# Ethernet_PMOD.net
KiCad netlist of a schematic drawn in Altium Designer
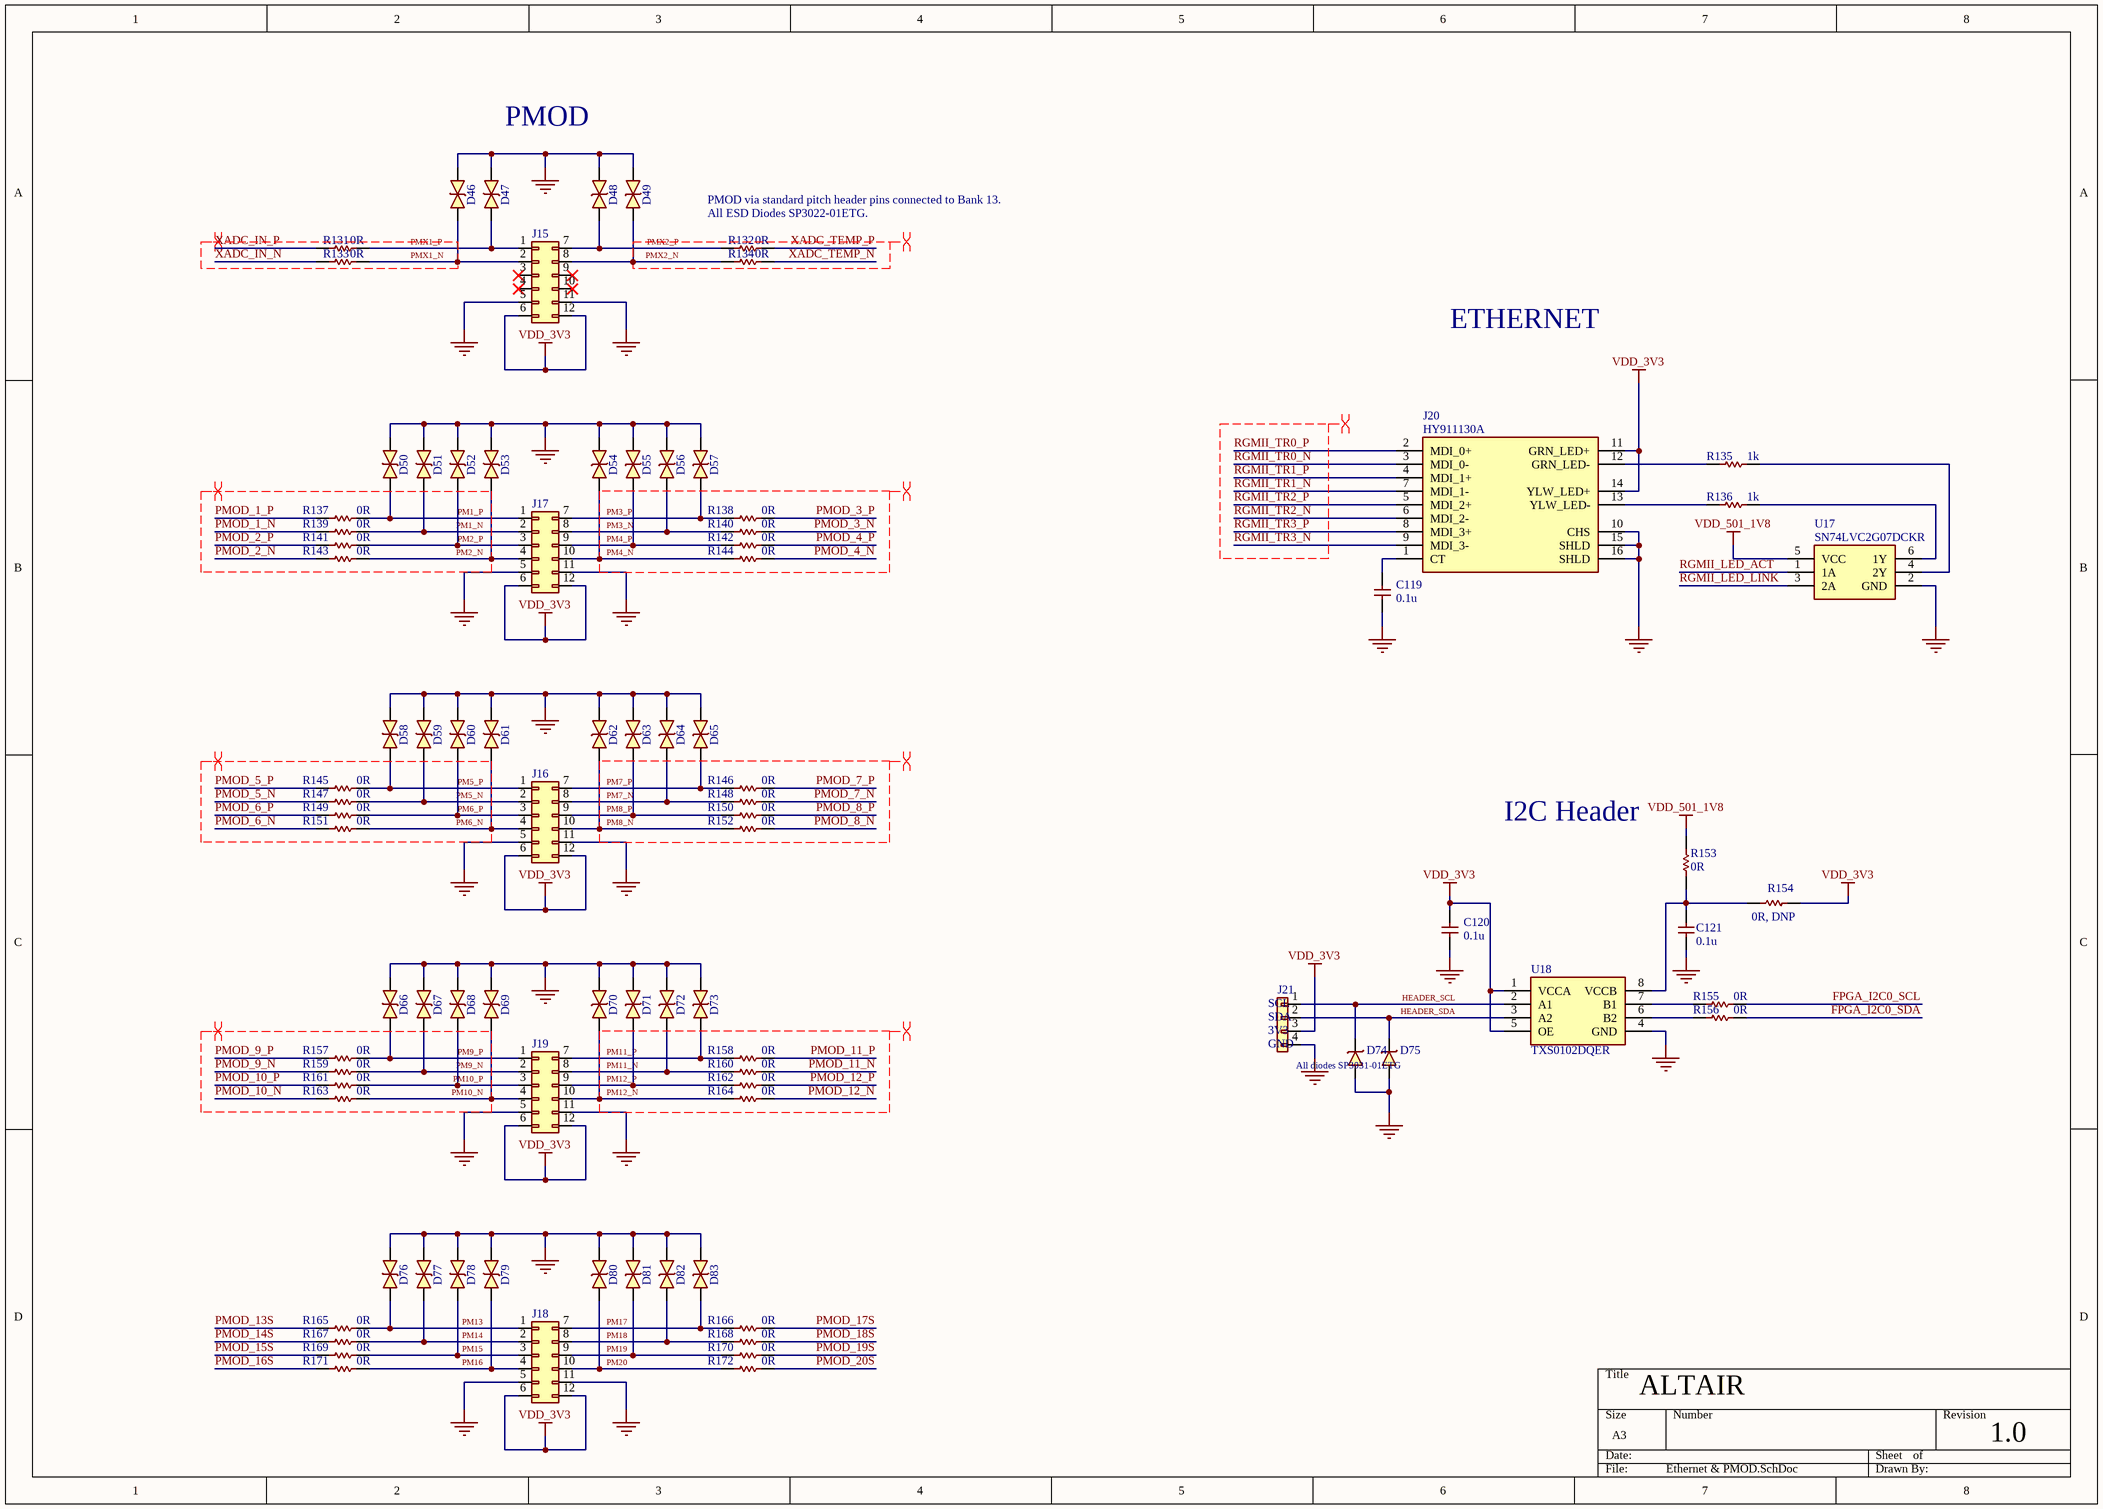
[diagram p0: Ethernet & PMOD.SchDoc]

(export (version "E")
  (design (tool "Eeschema 10.0.6"))
  (components
    (comp (ref "C119")
      (value "0.1u")
      (footprint "CAP_0402")
      (description "Capacitor SMD 0402")
      (fields (field (name "PART NO") "CL05B104KO5NNNC") (field (name "JLCPCB PART #") "C338112"))
      (libsource (lib "personalGenericLib") (part "CAP_0402"))
    )
    (comp (ref "C120")
      (value "0.1u")
      (footprint "CAP_0402")
      (description "Capacitor SMD 0402")
      (fields (field (name "PART NO") "CL05B104KO5NNNC") (field (name "JLCPCB PART #") "C338112"))
      (libsource (lib "personalGenericLib") (part "CAP_0402"))
    )
    (comp (ref "C121")
      (value "0.1u")
      (footprint "CAP_0402")
      (description "Capacitor SMD 0402")
      (fields (field (name "PART NO") "CL05B104KO5NNNC") (field (name "JLCPCB PART #") "C338112"))
      (libsource (lib "personalGenericLib") (part "CAP_0402"))
    )
    (comp (ref "D46")
      (value "SP3022-01ETG")
      (footprint "SP302201ETGNM")
      (description "TVS Diode (Bi-directional)")
      (fields (field (name "JLCPCB PART #") "C126840"))
      (libsource (lib "personalGenericLib") (part "SP3022-01ETG"))
    )
    (comp (ref "D47")
      (value "SP3022-01ETG")
      (footprint "SP302201ETGNM")
      (description "TVS Diode (Bi-directional)")
      (fields (field (name "JLCPCB PART #") "C126840"))
      (libsource (lib "personalGenericLib") (part "SP3022-01ETG"))
    )
    (comp (ref "D48")
      (value "SP3022-01ETG")
      (footprint "SP302201ETGNM")
      (description "TVS Diode (Bi-directional)")
      (fields (field (name "JLCPCB PART #") "C126840"))
      (libsource (lib "personalGenericLib") (part "SP3022-01ETG"))
    )
    (comp (ref "D49")
      (value "SP3022-01ETG")
      (footprint "SP302201ETGNM")
      (description "TVS Diode (Bi-directional)")
      (fields (field (name "JLCPCB PART #") "C126840"))
      (libsource (lib "personalGenericLib") (part "SP3022-01ETG"))
    )
    (comp (ref "D50")
      (value "SP3022-01ETG")
      (footprint "SP302201ETGNM")
      (description "TVS Diode (Bi-directional)")
      (fields (field (name "JLCPCB PART #") "C126840"))
      (libsource (lib "personalGenericLib") (part "SP3022-01ETG"))
    )
    (comp (ref "D51")
      (value "SP3022-01ETG")
      (footprint "SP302201ETGNM")
      (description "TVS Diode (Bi-directional)")
      (fields (field (name "JLCPCB PART #") "C126840"))
      (libsource (lib "personalGenericLib") (part "SP3022-01ETG"))
    )
    (comp (ref "D52")
      (value "SP3022-01ETG")
      (footprint "SP302201ETGNM")
      (description "TVS Diode (Bi-directional)")
      (fields (field (name "JLCPCB PART #") "C126840"))
      (libsource (lib "personalGenericLib") (part "SP3022-01ETG"))
    )
    (comp (ref "D53")
      (value "SP3022-01ETG")
      (footprint "SP302201ETGNM")
      (description "TVS Diode (Bi-directional)")
      (fields (field (name "JLCPCB PART #") "C126840"))
      (libsource (lib "personalGenericLib") (part "SP3022-01ETG"))
    )
    (comp (ref "D54")
      (value "SP3022-01ETG")
      (footprint "SP302201ETGNM")
      (description "TVS Diode (Bi-directional)")
      (fields (field (name "JLCPCB PART #") "C126840"))
      (libsource (lib "personalGenericLib") (part "SP3022-01ETG"))
    )
    (comp (ref "D55")
      (value "SP3022-01ETG")
      (footprint "SP302201ETGNM")
      (description "TVS Diode (Bi-directional)")
      (fields (field (name "JLCPCB PART #") "C126840"))
      (libsource (lib "personalGenericLib") (part "SP3022-01ETG"))
    )
    (comp (ref "D56")
      (value "SP3022-01ETG")
      (footprint "SP302201ETGNM")
      (description "TVS Diode (Bi-directional)")
      (fields (field (name "JLCPCB PART #") "C126840"))
      (libsource (lib "personalGenericLib") (part "SP3022-01ETG"))
    )
    (comp (ref "D57")
      (value "SP3022-01ETG")
      (footprint "SP302201ETGNM")
      (description "TVS Diode (Bi-directional)")
      (fields (field (name "JLCPCB PART #") "C126840"))
      (libsource (lib "personalGenericLib") (part "SP3022-01ETG"))
    )
    (comp (ref "D58")
      (value "SP3022-01ETG")
      (footprint "SP302201ETGNM")
      (description "TVS Diode (Bi-directional)")
      (fields (field (name "JLCPCB PART #") "C126840"))
      (libsource (lib "personalGenericLib") (part "SP3022-01ETG"))
    )
    (comp (ref "D59")
      (value "SP3022-01ETG")
      (footprint "SP302201ETGNM")
      (description "TVS Diode (Bi-directional)")
      (fields (field (name "JLCPCB PART #") "C126840"))
      (libsource (lib "personalGenericLib") (part "SP3022-01ETG"))
    )
    (comp (ref "D60")
      (value "SP3022-01ETG")
      (footprint "SP302201ETGNM")
      (description "TVS Diode (Bi-directional)")
      (fields (field (name "JLCPCB PART #") "C126840"))
      (libsource (lib "personalGenericLib") (part "SP3022-01ETG"))
    )
    (comp (ref "D61")
      (value "SP3022-01ETG")
      (footprint "SP302201ETGNM")
      (description "TVS Diode (Bi-directional)")
      (fields (field (name "JLCPCB PART #") "C126840"))
      (libsource (lib "personalGenericLib") (part "SP3022-01ETG"))
    )
    (comp (ref "D62")
      (value "SP3022-01ETG")
      (footprint "SP302201ETGNM")
      (description "TVS Diode (Bi-directional)")
      (fields (field (name "JLCPCB PART #") "C126840"))
      (libsource (lib "personalGenericLib") (part "SP3022-01ETG"))
    )
    (comp (ref "D63")
      (value "SP3022-01ETG")
      (footprint "SP302201ETGNM")
      (description "TVS Diode (Bi-directional)")
      (fields (field (name "JLCPCB PART #") "C126840"))
      (libsource (lib "personalGenericLib") (part "SP3022-01ETG"))
    )
    (comp (ref "D64")
      (value "SP3022-01ETG")
      (footprint "SP302201ETGNM")
      (description "TVS Diode (Bi-directional)")
      (fields (field (name "JLCPCB PART #") "C126840"))
      (libsource (lib "personalGenericLib") (part "SP3022-01ETG"))
    )
    (comp (ref "D65")
      (value "SP3022-01ETG")
      (footprint "SP302201ETGNM")
      (description "TVS Diode (Bi-directional)")
      (fields (field (name "JLCPCB PART #") "C126840"))
      (libsource (lib "personalGenericLib") (part "SP3022-01ETG"))
    )
    (comp (ref "D66")
      (value "SP3022-01ETG")
      (footprint "SP302201ETGNM")
      (description "TVS Diode (Bi-directional)")
      (fields (field (name "JLCPCB PART #") "C126840"))
      (libsource (lib "personalGenericLib") (part "SP3022-01ETG"))
    )
    (comp (ref "D67")
      (value "SP3022-01ETG")
      (footprint "SP302201ETGNM")
      (description "TVS Diode (Bi-directional)")
      (fields (field (name "JLCPCB PART #") "C126840"))
      (libsource (lib "personalGenericLib") (part "SP3022-01ETG"))
    )
    (comp (ref "D68")
      (value "SP3022-01ETG")
      (footprint "SP302201ETGNM")
      (description "TVS Diode (Bi-directional)")
      (fields (field (name "JLCPCB PART #") "C126840"))
      (libsource (lib "personalGenericLib") (part "SP3022-01ETG"))
    )
    (comp (ref "D69")
      (value "SP3022-01ETG")
      (footprint "SP302201ETGNM")
      (description "TVS Diode (Bi-directional)")
      (fields (field (name "JLCPCB PART #") "C126840"))
      (libsource (lib "personalGenericLib") (part "SP3022-01ETG"))
    )
    (comp (ref "D70")
      (value "SP3022-01ETG")
      (footprint "SP302201ETGNM")
      (description "TVS Diode (Bi-directional)")
      (fields (field (name "JLCPCB PART #") "C126840"))
      (libsource (lib "personalGenericLib") (part "SP3022-01ETG"))
    )
    (comp (ref "D71")
      (value "SP3022-01ETG")
      (footprint "SP302201ETGNM")
      (description "TVS Diode (Bi-directional)")
      (fields (field (name "JLCPCB PART #") "C126840"))
      (libsource (lib "personalGenericLib") (part "SP3022-01ETG"))
    )
    (comp (ref "D72")
      (value "SP3022-01ETG")
      (footprint "SP302201ETGNM")
      (description "TVS Diode (Bi-directional)")
      (fields (field (name "JLCPCB PART #") "C126840"))
      (libsource (lib "personalGenericLib") (part "SP3022-01ETG"))
    )
    (comp (ref "D73")
      (value "SP3022-01ETG")
      (footprint "SP302201ETGNM")
      (description "TVS Diode (Bi-directional)")
      (fields (field (name "JLCPCB PART #") "C126840"))
      (libsource (lib "personalGenericLib") (part "SP3022-01ETG"))
    )
    (comp (ref "D74")
      (value "SP3031-01ETG")
      (footprint "SP303101ETG")
      (description "TVS Diode (Uni-directional)")
      (fields (field (name "JLCPCB PART #") "C207283"))
      (libsource (lib "personalGenericLib") (part "SP3031-01ETG"))
    )
    (comp (ref "D75")
      (value "SP3031-01ETG")
      (footprint "SP303101ETG")
      (description "TVS Diode (Uni-directional)")
      (fields (field (name "JLCPCB PART #") "C207283"))
      (libsource (lib "personalGenericLib") (part "SP3031-01ETG"))
    )
    (comp (ref "D76")
      (value "SP3022-01ETG")
      (footprint "SP302201ETGNM")
      (description "TVS Diode (Bi-directional)")
      (fields (field (name "JLCPCB PART #") "C126840"))
      (libsource (lib "personalGenericLib") (part "SP3022-01ETG"))
    )
    (comp (ref "D77")
      (value "SP3022-01ETG")
      (footprint "SP302201ETGNM")
      (description "TVS Diode (Bi-directional)")
      (fields (field (name "JLCPCB PART #") "C126840"))
      (libsource (lib "personalGenericLib") (part "SP3022-01ETG"))
    )
    (comp (ref "D78")
      (value "SP3022-01ETG")
      (footprint "SP302201ETGNM")
      (description "TVS Diode (Bi-directional)")
      (fields (field (name "JLCPCB PART #") "C126840"))
      (libsource (lib "personalGenericLib") (part "SP3022-01ETG"))
    )
    (comp (ref "D79")
      (value "SP3022-01ETG")
      (footprint "SP302201ETGNM")
      (description "TVS Diode (Bi-directional)")
      (fields (field (name "JLCPCB PART #") "C126840"))
      (libsource (lib "personalGenericLib") (part "SP3022-01ETG"))
    )
    (comp (ref "D80")
      (value "SP3022-01ETG")
      (footprint "SP302201ETGNM")
      (description "TVS Diode (Bi-directional)")
      (fields (field (name "JLCPCB PART #") "C126840"))
      (libsource (lib "personalGenericLib") (part "SP3022-01ETG"))
    )
    (comp (ref "D81")
      (value "SP3022-01ETG")
      (footprint "SP302201ETGNM")
      (description "TVS Diode (Bi-directional)")
      (fields (field (name "JLCPCB PART #") "C126840"))
      (libsource (lib "personalGenericLib") (part "SP3022-01ETG"))
    )
    (comp (ref "D82")
      (value "SP3022-01ETG")
      (footprint "SP302201ETGNM")
      (description "TVS Diode (Bi-directional)")
      (fields (field (name "JLCPCB PART #") "C126840"))
      (libsource (lib "personalGenericLib") (part "SP3022-01ETG"))
    )
    (comp (ref "D83")
      (value "SP3022-01ETG")
      (footprint "SP302201ETGNM")
      (description "TVS Diode (Bi-directional)")
      (fields (field (name "JLCPCB PART #") "C126840"))
      (libsource (lib "personalGenericLib") (part "SP3022-01ETG"))
    )
    (comp (ref "J15")
      (value "PMOD_HEADER")
      (footprint "PMOD_HEADER")
      (description "NON-Standard 2x6 pin 2.54mm pitch connector. Right Angle")
      (fields (field (name "JLCPCB PART #") "C22373932") (field (name "PART NO") "HC-PM254-8.5H-2x6PW"))
      (libsource (lib "personalGenericLib") (part "PMOD_HEADER"))
    )
    (comp (ref "J16")
      (value "PMOD_HEADER")
      (footprint "PMOD_HEADER")
      (description "NON-Standard 2x6 pin 2.54mm pitch connector. Right Angle")
      (fields (field (name "JLCPCB PART #") "C22373932") (field (name "PART NO") "HC-PM254-8.5H-2x6PW"))
      (libsource (lib "personalGenericLib") (part "PMOD_HEADER"))
    )
    (comp (ref "J17")
      (value "PMOD_HEADER")
      (footprint "PMOD_HEADER")
      (description "NON-Standard 2x6 pin 2.54mm pitch connector. Right Angle")
      (fields (field (name "JLCPCB PART #") "C22373932") (field (name "PART NO") "HC-PM254-8.5H-2x6PW"))
      (libsource (lib "personalGenericLib") (part "PMOD_HEADER"))
    )
    (comp (ref "J18")
      (value "PMOD_HEADER")
      (footprint "PMOD_HEADER")
      (description "NON-Standard 2x6 pin 2.54mm pitch connector. Right Angle")
      (libsource (lib "personalGenericLib") (part "PMOD_HEADER"))
    )
    (comp (ref "J19")
      (value "PMOD_HEADER")
      (footprint "PMOD_HEADER")
      (description "NON-Standard 2x6 pin 2.54mm pitch connector. Right Angle")
      (fields (field (name "JLCPCB PART #") "C22373932") (field (name "PART NO") "HC-PM254-8.5H-2x6PW"))
      (libsource (lib "personalGenericLib") (part "PMOD_HEADER"))
    )
    (comp (ref "J20")
      (value "HY911130A")
      (footprint "HY911130A")
      (description "Ethernet Connector")
      (fields (field (name "JLCPCB PART #") "C55679"))
      (libsource (lib "personalGenericLib") (part "HY911130A"))
    )
    (comp (ref "J21")
      (value "4xHeader")
      (footprint "HDRV4W95P0X254_1X4_1016X254X854P")
      (description "Standard 4 pin 2.54mm pitch connector")
      (fields (field (name "JLCPCB PART #") "C706876") (field (name "PART NO") "X6511WV-04H-C60D30"))
      (libsource (lib "personalGenericLib") (part "4xHeader"))
    )
    (comp (ref "R131")
      (value "0R")
      (footprint "RES_0402")
      (description "Resistor SMD 0402")
      (fields (field (name "JLCPCB PART #") "C60485") (field (name "PART NO") "RC0402JR-070RL"))
      (libsource (lib "personalGenericLib") (part "RES_0402"))
    )
    (comp (ref "R132")
      (value "0R")
      (footprint "RES_0402")
      (description "Resistor SMD 0402")
      (fields (field (name "JLCPCB PART #") "C60485") (field (name "PART NO") "RC0402JR-070RL"))
      (libsource (lib "personalGenericLib") (part "RES_0402"))
    )
    (comp (ref "R133")
      (value "0R")
      (footprint "RES_0402")
      (description "Resistor SMD 0402")
      (fields (field (name "JLCPCB PART #") "C60485") (field (name "PART NO") "RC0402JR-070RL"))
      (libsource (lib "personalGenericLib") (part "RES_0402"))
    )
    (comp (ref "R134")
      (value "0R")
      (footprint "RES_0402")
      (description "Resistor SMD 0402")
      (fields (field (name "JLCPCB PART #") "C60485") (field (name "PART NO") "RC0402JR-070RL"))
      (libsource (lib "personalGenericLib") (part "RES_0402"))
    )
    (comp (ref "R135")
      (value "1k")
      (footprint "RES_0402")
      (description "Resistor SMD 0402")
      (fields (field (name "JLCPCB PART #") "C105637") (field (name "PART NO") "RC0402JR-071KL"))
      (libsource (lib "personalGenericLib") (part "RES_0402"))
    )
    (comp (ref "R136")
      (value "1k")
      (footprint "RES_0402")
      (description "Resistor SMD 0402")
      (fields (field (name "JLCPCB PART #") "C105637") (field (name "PART NO") "RC0402JR-071KL"))
      (libsource (lib "personalGenericLib") (part "RES_0402"))
    )
    (comp (ref "R137")
      (value "0R")
      (footprint "RES_0402")
      (description "Resistor SMD 0402")
      (fields (field (name "JLCPCB PART #") "C60485") (field (name "PART NO") "RC0402JR-070RL"))
      (libsource (lib "personalGenericLib") (part "RES_0402"))
    )
    (comp (ref "R138")
      (value "0R")
      (footprint "RES_0402")
      (description "Resistor SMD 0402")
      (fields (field (name "JLCPCB PART #") "C60485") (field (name "PART NO") "RC0402JR-070RL"))
      (libsource (lib "personalGenericLib") (part "RES_0402"))
    )
    (comp (ref "R139")
      (value "0R")
      (footprint "RES_0402")
      (description "Resistor SMD 0402")
      (fields (field (name "JLCPCB PART #") "C60485") (field (name "PART NO") "RC0402JR-070RL"))
      (libsource (lib "personalGenericLib") (part "RES_0402"))
    )
    (comp (ref "R140")
      (value "0R")
      (footprint "RES_0402")
      (description "Resistor SMD 0402")
      (fields (field (name "JLCPCB PART #") "C60485") (field (name "PART NO") "RC0402JR-070RL"))
      (libsource (lib "personalGenericLib") (part "RES_0402"))
    )
    (comp (ref "R141")
      (value "0R")
      (footprint "RES_0402")
      (description "Resistor SMD 0402")
      (fields (field (name "JLCPCB PART #") "C60485") (field (name "PART NO") "RC0402JR-070RL"))
      (libsource (lib "personalGenericLib") (part "RES_0402"))
    )
    (comp (ref "R142")
      (value "0R")
      (footprint "RES_0402")
      (description "Resistor SMD 0402")
      (fields (field (name "JLCPCB PART #") "C60485") (field (name "PART NO") "RC0402JR-070RL"))
      (libsource (lib "personalGenericLib") (part "RES_0402"))
    )
    (comp (ref "R143")
      (value "0R")
      (footprint "RES_0402")
      (description "Resistor SMD 0402")
      (fields (field (name "JLCPCB PART #") "C60485") (field (name "PART NO") "RC0402JR-070RL"))
      (libsource (lib "personalGenericLib") (part "RES_0402"))
    )
    (comp (ref "R144")
      (value "0R")
      (footprint "RES_0402")
      (description "Resistor SMD 0402")
      (fields (field (name "JLCPCB PART #") "C60485") (field (name "PART NO") "RC0402JR-070RL"))
      (libsource (lib "personalGenericLib") (part "RES_0402"))
    )
    (comp (ref "R145")
      (value "0R")
      (footprint "RES_0402")
      (description "Resistor SMD 0402")
      (fields (field (name "JLCPCB PART #") "C60485") (field (name "PART NO") "RC0402JR-070RL"))
      (libsource (lib "personalGenericLib") (part "RES_0402"))
    )
    (comp (ref "R146")
      (value "0R")
      (footprint "RES_0402")
      (description "Resistor SMD 0402")
      (fields (field (name "JLCPCB PART #") "C60485") (field (name "PART NO") "RC0402JR-070RL"))
      (libsource (lib "personalGenericLib") (part "RES_0402"))
    )
    (comp (ref "R147")
      (value "0R")
      (footprint "RES_0402")
      (description "Resistor SMD 0402")
      (fields (field (name "JLCPCB PART #") "C60485") (field (name "PART NO") "RC0402JR-070RL"))
      (libsource (lib "personalGenericLib") (part "RES_0402"))
    )
    (comp (ref "R148")
      (value "0R")
      (footprint "RES_0402")
      (description "Resistor SMD 0402")
      (fields (field (name "JLCPCB PART #") "C60485") (field (name "PART NO") "RC0402JR-070RL"))
      (libsource (lib "personalGenericLib") (part "RES_0402"))
    )
    (comp (ref "R149")
      (value "0R")
      (footprint "RES_0402")
      (description "Resistor SMD 0402")
      (fields (field (name "JLCPCB PART #") "C60485") (field (name "PART NO") "RC0402JR-070RL"))
      (libsource (lib "personalGenericLib") (part "RES_0402"))
    )
    (comp (ref "R150")
      (value "0R")
      (footprint "RES_0402")
      (description "Resistor SMD 0402")
      (fields (field (name "JLCPCB PART #") "C60485") (field (name "PART NO") "RC0402JR-070RL"))
      (libsource (lib "personalGenericLib") (part "RES_0402"))
    )
    (comp (ref "R151")
      (value "0R")
      (footprint "RES_0402")
      (description "Resistor SMD 0402")
      (fields (field (name "JLCPCB PART #") "C60485") (field (name "PART NO") "RC0402JR-070RL"))
      (libsource (lib "personalGenericLib") (part "RES_0402"))
    )
    (comp (ref "R152")
      (value "0R")
      (footprint "RES_0402")
      (description "Resistor SMD 0402")
      (fields (field (name "JLCPCB PART #") "C60485") (field (name "PART NO") "RC0402JR-070RL"))
      (libsource (lib "personalGenericLib") (part "RES_0402"))
    )
    (comp (ref "R153")
      (value "0R")
      (footprint "RES_0402")
      (description "Resistor SMD 0402")
      (fields (field (name "JLCPCB PART #") "C60485") (field (name "PART NO") "RC0402JR-070RL"))
      (libsource (lib "personalGenericLib") (part "RES_0402"))
    )
    (comp (ref "R154")
      (value "0R, DNP")
      (footprint "RES_0402")
      (description "Resistor SMD 0402")
      (fields (field (name "JLCPCB PART #") "C60485") (field (name "PART NO") "RC0402JR-070RL"))
      (libsource (lib "personalGenericLib") (part "RES_0402"))
    )
    (comp (ref "R155")
      (value "0R")
      (footprint "RES_0402")
      (description "Resistor SMD 0402")
      (fields (field (name "JLCPCB PART #") "C60485") (field (name "PART NO") "RC0402JR-070RL"))
      (libsource (lib "personalGenericLib") (part "RES_0402"))
    )
    (comp (ref "R156")
      (value "0R")
      (footprint "RES_0402")
      (description "Resistor SMD 0402")
      (fields (field (name "JLCPCB PART #") "C60485") (field (name "PART NO") "RC0402JR-070RL"))
      (libsource (lib "personalGenericLib") (part "RES_0402"))
    )
    (comp (ref "R157")
      (value "0R")
      (footprint "RES_0402")
      (description "Resistor SMD 0402")
      (fields (field (name "JLCPCB PART #") "C60485") (field (name "PART NO") "RC0402JR-070RL"))
      (libsource (lib "personalGenericLib") (part "RES_0402"))
    )
    (comp (ref "R158")
      (value "0R")
      (footprint "RES_0402")
      (description "Resistor SMD 0402")
      (fields (field (name "JLCPCB PART #") "C60485") (field (name "PART NO") "RC0402JR-070RL"))
      (libsource (lib "personalGenericLib") (part "RES_0402"))
    )
    (comp (ref "R159")
      (value "0R")
      (footprint "RES_0402")
      (description "Resistor SMD 0402")
      (fields (field (name "JLCPCB PART #") "C60485") (field (name "PART NO") "RC0402JR-070RL"))
      (libsource (lib "personalGenericLib") (part "RES_0402"))
    )
    (comp (ref "R160")
      (value "0R")
      (footprint "RES_0402")
      (description "Resistor SMD 0402")
      (fields (field (name "JLCPCB PART #") "C60485") (field (name "PART NO") "RC0402JR-070RL"))
      (libsource (lib "personalGenericLib") (part "RES_0402"))
    )
    (comp (ref "R161")
      (value "0R")
      (footprint "RES_0402")
      (description "Resistor SMD 0402")
      (fields (field (name "JLCPCB PART #") "C60485") (field (name "PART NO") "RC0402JR-070RL"))
      (libsource (lib "personalGenericLib") (part "RES_0402"))
    )
    (comp (ref "R162")
      (value "0R")
      (footprint "RES_0402")
      (description "Resistor SMD 0402")
      (fields (field (name "JLCPCB PART #") "C60485") (field (name "PART NO") "RC0402JR-070RL"))
      (libsource (lib "personalGenericLib") (part "RES_0402"))
    )
    (comp (ref "R163")
      (value "0R")
      (footprint "RES_0402")
      (description "Resistor SMD 0402")
      (fields (field (name "JLCPCB PART #") "C60485") (field (name "PART NO") "RC0402JR-070RL"))
      (libsource (lib "personalGenericLib") (part "RES_0402"))
    )
    (comp (ref "R164")
      (value "0R")
      (footprint "RES_0402")
      (description "Resistor SMD 0402")
      (fields (field (name "JLCPCB PART #") "C60485") (field (name "PART NO") "RC0402JR-070RL"))
      (libsource (lib "personalGenericLib") (part "RES_0402"))
    )
    (comp (ref "R165")
      (value "0R")
      (footprint "RES_0402")
      (description "Resistor SMD 0402")
      (fields (field (name "JLCPCB PART #") "C60485") (field (name "PART NO") "RC0402JR-070RL"))
      (libsource (lib "personalGenericLib") (part "RES_0402"))
    )
    (comp (ref "R166")
      (value "0R")
      (footprint "RES_0402")
      (description "Resistor SMD 0402")
      (fields (field (name "JLCPCB PART #") "C60485") (field (name "PART NO") "RC0402JR-070RL"))
      (libsource (lib "personalGenericLib") (part "RES_0402"))
    )
    (comp (ref "R167")
      (value "0R")
      (footprint "RES_0402")
      (description "Resistor SMD 0402")
      (fields (field (name "JLCPCB PART #") "C60485") (field (name "PART NO") "RC0402JR-070RL"))
      (libsource (lib "personalGenericLib") (part "RES_0402"))
    )
    (comp (ref "R168")
      (value "0R")
      (footprint "RES_0402")
      (description "Resistor SMD 0402")
      (fields (field (name "JLCPCB PART #") "C60485") (field (name "PART NO") "RC0402JR-070RL"))
      (libsource (lib "personalGenericLib") (part "RES_0402"))
    )
    (comp (ref "R169")
      (value "0R")
      (footprint "RES_0402")
      (description "Resistor SMD 0402")
      (fields (field (name "JLCPCB PART #") "C60485") (field (name "PART NO") "RC0402JR-070RL"))
      (libsource (lib "personalGenericLib") (part "RES_0402"))
    )
    (comp (ref "R170")
      (value "0R")
      (footprint "RES_0402")
      (description "Resistor SMD 0402")
      (fields (field (name "JLCPCB PART #") "C60485") (field (name "PART NO") "RC0402JR-070RL"))
      (libsource (lib "personalGenericLib") (part "RES_0402"))
    )
    (comp (ref "R171")
      (value "0R")
      (footprint "RES_0402")
      (description "Resistor SMD 0402")
      (fields (field (name "JLCPCB PART #") "C60485") (field (name "PART NO") "RC0402JR-070RL"))
      (libsource (lib "personalGenericLib") (part "RES_0402"))
    )
    (comp (ref "R172")
      (value "0R")
      (footprint "RES_0402")
      (description "Resistor SMD 0402")
      (fields (field (name "JLCPCB PART #") "C60485") (field (name "PART NO") "RC0402JR-070RL"))
      (libsource (lib "personalGenericLib") (part "RES_0402"))
    )
    (comp (ref "U17")
      (value "SN74LVC2G07DCKR")
      (footprint "SOT65P210X110-6N")
      (description "Buffer Gate 1 input 1 output")
      (fields (field (name "JLCPCB PART #") "C7849"))
      (libsource (lib "personalGenericLib") (part "SN74LVC2G07DCKR"))
    )
    (comp (ref "U18")
      (value "TXS0102DQER")
      (footprint "SON35P100X140X40-8N")
      (description "I2C UART Voltage Level Translator")
      (fields (field (name "JLCPCB PART #") "C2652935"))
      (libsource (lib "personalGenericLib") (part "TXS0102DQER"))
    )
  )
  (nets
    (net (code "1") (name "/FPGA_I2C0_SCL") (class "Default")
      (node (ref "R155") (pin "2") (pinfunction "2_2") (pintype "passive"))
    )
    (net (code "2") (name "/FPGA_I2C0_SDA") (class "Default")
      (node (ref "R156") (pin "2") (pinfunction "2_2") (pintype "passive"))
    )
    (net (code "3") (name "/HEADER_SCL") (class "Default")
      (node (ref "D74") (pin "1") (pinfunction "K_1") (pintype "passive"))
      (node (ref "J21") (pin "1") (pinfunction "1_1") (pintype "passive"))
      (node (ref "U18") (pin "2") (pinfunction "A1_2") (pintype "passive"))
    )
    (net (code "4") (name "/HEADER_SDA") (class "Default")
      (node (ref "D75") (pin "1") (pinfunction "K_1") (pintype "passive"))
      (node (ref "J21") (pin "2") (pinfunction "2_2") (pintype "passive"))
      (node (ref "U18") (pin "3") (pinfunction "A2_3") (pintype "passive"))
    )
    (net (code "5") (name "/PM1_N") (class "Default")
      (node (ref "D51") (pin "2") (pinfunction "2_2") (pintype "passive"))
      (node (ref "J17") (pin "2") (pinfunction "2_2") (pintype "passive"))
      (node (ref "R139") (pin "2") (pinfunction "2_2") (pintype "passive"))
    )
    (net (code "6") (name "/PM1_P") (class "Default")
      (node (ref "D50") (pin "2") (pinfunction "2_2") (pintype "passive"))
      (node (ref "J17") (pin "1") (pinfunction "1_1") (pintype "passive"))
      (node (ref "R137") (pin "2") (pinfunction "2_2") (pintype "passive"))
    )
    (net (code "7") (name "/PM2_N") (class "Default")
      (node (ref "D53") (pin "2") (pinfunction "2_2") (pintype "passive"))
      (node (ref "J17") (pin "4") (pinfunction "4_4") (pintype "passive"))
      (node (ref "R143") (pin "2") (pinfunction "2_2") (pintype "passive"))
    )
    (net (code "8") (name "/PM2_P") (class "Default")
      (node (ref "D52") (pin "2") (pinfunction "2_2") (pintype "passive"))
      (node (ref "J17") (pin "3") (pinfunction "3_3") (pintype "passive"))
      (node (ref "R141") (pin "2") (pinfunction "2_2") (pintype "passive"))
    )
    (net (code "9") (name "/PM3_N") (class "Default")
      (node (ref "D56") (pin "2") (pinfunction "2_2") (pintype "passive"))
      (node (ref "J17") (pin "8") (pinfunction "8_8") (pintype "passive"))
      (node (ref "R140") (pin "1") (pinfunction "1_1") (pintype "passive"))
    )
    (net (code "10") (name "/PM3_P") (class "Default")
      (node (ref "D57") (pin "2") (pinfunction "2_2") (pintype "passive"))
      (node (ref "J17") (pin "7") (pinfunction "7_7") (pintype "passive"))
      (node (ref "R138") (pin "1") (pinfunction "1_1") (pintype "passive"))
    )
    (net (code "11") (name "/PM4_N") (class "Default")
      (node (ref "D54") (pin "2") (pinfunction "2_2") (pintype "passive"))
      (node (ref "J17") (pin "10") (pinfunction "10_10") (pintype "passive"))
      (node (ref "R144") (pin "1") (pinfunction "1_1") (pintype "passive"))
    )
    (net (code "12") (name "/PM4_P") (class "Default")
      (node (ref "D55") (pin "2") (pinfunction "2_2") (pintype "passive"))
      (node (ref "J17") (pin "9") (pinfunction "9_9") (pintype "passive"))
      (node (ref "R142") (pin "1") (pinfunction "1_1") (pintype "passive"))
    )
    (net (code "13") (name "/PM5_N") (class "Default")
      (node (ref "D59") (pin "2") (pinfunction "2_2") (pintype "passive"))
      (node (ref "J16") (pin "2") (pinfunction "2_2") (pintype "passive"))
      (node (ref "R147") (pin "2") (pinfunction "2_2") (pintype "passive"))
    )
    (net (code "14") (name "/PM5_P") (class "Default")
      (node (ref "D58") (pin "2") (pinfunction "2_2") (pintype "passive"))
      (node (ref "J16") (pin "1") (pinfunction "1_1") (pintype "passive"))
      (node (ref "R145") (pin "2") (pinfunction "2_2") (pintype "passive"))
    )
    (net (code "15") (name "/PM6_N") (class "Default")
      (node (ref "D61") (pin "2") (pinfunction "2_2") (pintype "passive"))
      (node (ref "J16") (pin "4") (pinfunction "4_4") (pintype "passive"))
      (node (ref "R151") (pin "2") (pinfunction "2_2") (pintype "passive"))
    )
    (net (code "16") (name "/PM6_P") (class "Default")
      (node (ref "D60") (pin "2") (pinfunction "2_2") (pintype "passive"))
      (node (ref "J16") (pin "3") (pinfunction "3_3") (pintype "passive"))
      (node (ref "R149") (pin "2") (pinfunction "2_2") (pintype "passive"))
    )
    (net (code "17") (name "/PM7_N") (class "Default")
      (node (ref "D64") (pin "2") (pinfunction "2_2") (pintype "passive"))
      (node (ref "J16") (pin "8") (pinfunction "8_8") (pintype "passive"))
      (node (ref "R148") (pin "1") (pinfunction "1_1") (pintype "passive"))
    )
    (net (code "18") (name "/PM7_P") (class "Default")
      (node (ref "D65") (pin "2") (pinfunction "2_2") (pintype "passive"))
      (node (ref "J16") (pin "7") (pinfunction "7_7") (pintype "passive"))
      (node (ref "R146") (pin "1") (pinfunction "1_1") (pintype "passive"))
    )
    (net (code "19") (name "/PM8_N") (class "Default")
      (node (ref "D62") (pin "2") (pinfunction "2_2") (pintype "passive"))
      (node (ref "J16") (pin "10") (pinfunction "10_10") (pintype "passive"))
      (node (ref "R152") (pin "1") (pinfunction "1_1") (pintype "passive"))
    )
    (net (code "20") (name "/PM8_P") (class "Default")
      (node (ref "D63") (pin "2") (pinfunction "2_2") (pintype "passive"))
      (node (ref "J16") (pin "9") (pinfunction "9_9") (pintype "passive"))
      (node (ref "R150") (pin "1") (pinfunction "1_1") (pintype "passive"))
    )
    (net (code "21") (name "/PM9_N") (class "Default")
      (node (ref "D67") (pin "2") (pinfunction "2_2") (pintype "passive"))
      (node (ref "J19") (pin "2") (pinfunction "2_2") (pintype "passive"))
      (node (ref "R159") (pin "2") (pinfunction "2_2") (pintype "passive"))
    )
    (net (code "22") (name "/PM9_P") (class "Default")
      (node (ref "D66") (pin "2") (pinfunction "2_2") (pintype "passive"))
      (node (ref "J19") (pin "1") (pinfunction "1_1") (pintype "passive"))
      (node (ref "R157") (pin "2") (pinfunction "2_2") (pintype "passive"))
    )
    (net (code "23") (name "/PM10_N") (class "Default")
      (node (ref "D69") (pin "2") (pinfunction "2_2") (pintype "passive"))
      (node (ref "J19") (pin "4") (pinfunction "4_4") (pintype "passive"))
      (node (ref "R163") (pin "2") (pinfunction "2_2") (pintype "passive"))
    )
    (net (code "24") (name "/PM10_P") (class "Default")
      (node (ref "D68") (pin "2") (pinfunction "2_2") (pintype "passive"))
      (node (ref "J19") (pin "3") (pinfunction "3_3") (pintype "passive"))
      (node (ref "R161") (pin "2") (pinfunction "2_2") (pintype "passive"))
    )
    (net (code "25") (name "/PM11_N") (class "Default")
      (node (ref "D72") (pin "2") (pinfunction "2_2") (pintype "passive"))
      (node (ref "J19") (pin "8") (pinfunction "8_8") (pintype "passive"))
      (node (ref "R160") (pin "1") (pinfunction "1_1") (pintype "passive"))
    )
    (net (code "26") (name "/PM11_P") (class "Default")
      (node (ref "D73") (pin "2") (pinfunction "2_2") (pintype "passive"))
      (node (ref "J19") (pin "7") (pinfunction "7_7") (pintype "passive"))
      (node (ref "R158") (pin "1") (pinfunction "1_1") (pintype "passive"))
    )
    (net (code "27") (name "/PM12_N") (class "Default")
      (node (ref "D70") (pin "2") (pinfunction "2_2") (pintype "passive"))
      (node (ref "J19") (pin "10") (pinfunction "10_10") (pintype "passive"))
      (node (ref "R164") (pin "1") (pinfunction "1_1") (pintype "passive"))
    )
    (net (code "28") (name "/PM12_P") (class "Default")
      (node (ref "D71") (pin "2") (pinfunction "2_2") (pintype "passive"))
      (node (ref "J19") (pin "9") (pinfunction "9_9") (pintype "passive"))
      (node (ref "R162") (pin "1") (pinfunction "1_1") (pintype "passive"))
    )
    (net (code "29") (name "/PM13") (class "Default")
      (node (ref "D76") (pin "2") (pinfunction "2_2") (pintype "passive"))
      (node (ref "J18") (pin "1") (pinfunction "1_1") (pintype "passive"))
      (node (ref "R165") (pin "2") (pinfunction "2_2") (pintype "passive"))
    )
    (net (code "30") (name "/PM14") (class "Default")
      (node (ref "D77") (pin "2") (pinfunction "2_2") (pintype "passive"))
      (node (ref "J18") (pin "2") (pinfunction "2_2") (pintype "passive"))
      (node (ref "R167") (pin "2") (pinfunction "2_2") (pintype "passive"))
    )
    (net (code "31") (name "/PM15") (class "Default")
      (node (ref "D78") (pin "2") (pinfunction "2_2") (pintype "passive"))
      (node (ref "J18") (pin "3") (pinfunction "3_3") (pintype "passive"))
      (node (ref "R169") (pin "2") (pinfunction "2_2") (pintype "passive"))
    )
    (net (code "32") (name "/PM16") (class "Default")
      (node (ref "D79") (pin "2") (pinfunction "2_2") (pintype "passive"))
      (node (ref "J18") (pin "4") (pinfunction "4_4") (pintype "passive"))
      (node (ref "R171") (pin "2") (pinfunction "2_2") (pintype "passive"))
    )
    (net (code "33") (name "/PM17") (class "Default")
      (node (ref "D83") (pin "2") (pinfunction "2_2") (pintype "passive"))
      (node (ref "J18") (pin "7") (pinfunction "7_7") (pintype "passive"))
      (node (ref "R166") (pin "1") (pinfunction "1_1") (pintype "passive"))
    )
    (net (code "34") (name "/PM18") (class "Default")
      (node (ref "D82") (pin "2") (pinfunction "2_2") (pintype "passive"))
      (node (ref "J18") (pin "8") (pinfunction "8_8") (pintype "passive"))
      (node (ref "R168") (pin "1") (pinfunction "1_1") (pintype "passive"))
    )
    (net (code "35") (name "/PM19") (class "Default")
      (node (ref "D81") (pin "2") (pinfunction "2_2") (pintype "passive"))
      (node (ref "J18") (pin "9") (pinfunction "9_9") (pintype "passive"))
      (node (ref "R170") (pin "1") (pinfunction "1_1") (pintype "passive"))
    )
    (net (code "36") (name "/PM20") (class "Default")
      (node (ref "D80") (pin "2") (pinfunction "2_2") (pintype "passive"))
      (node (ref "J18") (pin "10") (pinfunction "10_10") (pintype "passive"))
      (node (ref "R172") (pin "1") (pinfunction "1_1") (pintype "passive"))
    )
    (net (code "37") (name "/PMOD_1_N") (class "Default")
      (node (ref "R139") (pin "1") (pinfunction "1_1") (pintype "passive"))
    )
    (net (code "38") (name "/PMOD_1_P") (class "Default")
      (node (ref "R137") (pin "1") (pinfunction "1_1") (pintype "passive"))
    )
    (net (code "39") (name "/PMOD_2_N") (class "Default")
      (node (ref "R143") (pin "1") (pinfunction "1_1") (pintype "passive"))
    )
    (net (code "40") (name "/PMOD_2_P") (class "Default")
      (node (ref "R141") (pin "1") (pinfunction "1_1") (pintype "passive"))
    )
    (net (code "41") (name "/PMOD_3_N") (class "Default")
      (node (ref "R140") (pin "2") (pinfunction "2_2") (pintype "passive"))
    )
    (net (code "42") (name "/PMOD_3_P") (class "Default")
      (node (ref "R138") (pin "2") (pinfunction "2_2") (pintype "passive"))
    )
    (net (code "43") (name "/PMOD_4_N") (class "Default")
      (node (ref "R144") (pin "2") (pinfunction "2_2") (pintype "passive"))
    )
    (net (code "44") (name "/PMOD_4_P") (class "Default")
      (node (ref "R142") (pin "2") (pinfunction "2_2") (pintype "passive"))
    )
    (net (code "45") (name "/PMOD_5_N") (class "Default")
      (node (ref "R147") (pin "1") (pinfunction "1_1") (pintype "passive"))
    )
    (net (code "46") (name "/PMOD_5_P") (class "Default")
      (node (ref "R145") (pin "1") (pinfunction "1_1") (pintype "passive"))
    )
    (net (code "47") (name "/PMOD_6_N") (class "Default")
      (node (ref "R151") (pin "1") (pinfunction "1_1") (pintype "passive"))
    )
    (net (code "48") (name "/PMOD_6_P") (class "Default")
      (node (ref "R149") (pin "1") (pinfunction "1_1") (pintype "passive"))
    )
    (net (code "49") (name "/PMOD_7_N") (class "Default")
      (node (ref "R148") (pin "2") (pinfunction "2_2") (pintype "passive"))
    )
    (net (code "50") (name "/PMOD_7_P") (class "Default")
      (node (ref "R146") (pin "2") (pinfunction "2_2") (pintype "passive"))
    )
    (net (code "51") (name "/PMOD_8_N") (class "Default")
      (node (ref "R152") (pin "2") (pinfunction "2_2") (pintype "passive"))
    )
    (net (code "52") (name "/PMOD_8_P") (class "Default")
      (node (ref "R150") (pin "2") (pinfunction "2_2") (pintype "passive"))
    )
    (net (code "53") (name "/PMOD_9_N") (class "Default")
      (node (ref "R159") (pin "1") (pinfunction "1_1") (pintype "passive"))
    )
    (net (code "54") (name "/PMOD_9_P") (class "Default")
      (node (ref "R157") (pin "1") (pinfunction "1_1") (pintype "passive"))
    )
    (net (code "55") (name "/PMOD_10_N") (class "Default")
      (node (ref "R163") (pin "1") (pinfunction "1_1") (pintype "passive"))
    )
    (net (code "56") (name "/PMOD_10_P") (class "Default")
      (node (ref "R161") (pin "1") (pinfunction "1_1") (pintype "passive"))
    )
    (net (code "57") (name "/PMOD_11_N") (class "Default")
      (node (ref "R160") (pin "2") (pinfunction "2_2") (pintype "passive"))
    )
    (net (code "58") (name "/PMOD_11_P") (class "Default")
      (node (ref "R158") (pin "2") (pinfunction "2_2") (pintype "passive"))
    )
    (net (code "59") (name "/PMOD_12_N") (class "Default")
      (node (ref "R164") (pin "2") (pinfunction "2_2") (pintype "passive"))
    )
    (net (code "60") (name "/PMOD_12_P") (class "Default")
      (node (ref "R162") (pin "2") (pinfunction "2_2") (pintype "passive"))
    )
    (net (code "61") (name "/PMOD_13S") (class "Default")
      (node (ref "R165") (pin "1") (pinfunction "1_1") (pintype "passive"))
    )
    (net (code "62") (name "/PMOD_14S") (class "Default")
      (node (ref "R167") (pin "1") (pinfunction "1_1") (pintype "passive"))
    )
    (net (code "63") (name "/PMOD_15S") (class "Default")
      (node (ref "R169") (pin "1") (pinfunction "1_1") (pintype "passive"))
    )
    (net (code "64") (name "/PMOD_16S") (class "Default")
      (node (ref "R171") (pin "1") (pinfunction "1_1") (pintype "passive"))
    )
    (net (code "65") (name "/PMOD_17S") (class "Default")
      (node (ref "R166") (pin "2") (pinfunction "2_2") (pintype "passive"))
    )
    (net (code "66") (name "/PMOD_18S") (class "Default")
      (node (ref "R168") (pin "2") (pinfunction "2_2") (pintype "passive"))
    )
    (net (code "67") (name "/PMOD_19S") (class "Default")
      (node (ref "R170") (pin "2") (pinfunction "2_2") (pintype "passive"))
    )
    (net (code "68") (name "/PMOD_20S") (class "Default")
      (node (ref "R172") (pin "2") (pinfunction "2_2") (pintype "passive"))
    )
    (net (code "69") (name "/PMX1_N") (class "Default")
      (node (ref "D46") (pin "2") (pinfunction "2_2") (pintype "passive"))
      (node (ref "J15") (pin "2") (pinfunction "2_2") (pintype "passive"))
      (node (ref "R133") (pin "2") (pinfunction "2_2") (pintype "passive"))
    )
    (net (code "70") (name "/PMX1_P") (class "Default")
      (node (ref "D47") (pin "2") (pinfunction "2_2") (pintype "passive"))
      (node (ref "J15") (pin "1") (pinfunction "1_1") (pintype "passive"))
      (node (ref "R131") (pin "2") (pinfunction "2_2") (pintype "passive"))
    )
    (net (code "71") (name "/PMX2_N") (class "Default")
      (node (ref "D49") (pin "2") (pinfunction "2_2") (pintype "passive"))
      (node (ref "J15") (pin "8") (pinfunction "8_8") (pintype "passive"))
      (node (ref "R134") (pin "1") (pinfunction "1_1") (pintype "passive"))
    )
    (net (code "72") (name "/PMX2_P") (class "Default")
      (node (ref "D48") (pin "2") (pinfunction "2_2") (pintype "passive"))
      (node (ref "J15") (pin "7") (pinfunction "7_7") (pintype "passive"))
      (node (ref "R132") (pin "1") (pinfunction "1_1") (pintype "passive"))
    )
    (net (code "73") (name "/RGMII_LED_ACT") (class "Default")
      (node (ref "U17") (pin "1") (pinfunction "1A_1") (pintype "passive"))
    )
    (net (code "74") (name "/RGMII_LED_LINK") (class "Default")
      (node (ref "U17") (pin "3") (pinfunction "2A_3") (pintype "passive"))
    )
    (net (code "75") (name "/RGMII_TR0_N") (class "Default")
      (node (ref "J20") (pin "3") (pinfunction "MDI_0-_3") (pintype "passive"))
    )
    (net (code "76") (name "/RGMII_TR0_P") (class "Default")
      (node (ref "J20") (pin "2") (pinfunction "MDI_0+_2") (pintype "passive"))
    )
    (net (code "77") (name "/RGMII_TR1_N") (class "Default")
      (node (ref "J20") (pin "7") (pinfunction "MDI_1-_7") (pintype "passive"))
    )
    (net (code "78") (name "/RGMII_TR1_P") (class "Default")
      (node (ref "J20") (pin "4") (pinfunction "MDI_1+_4") (pintype "passive"))
    )
    (net (code "79") (name "/RGMII_TR2_N") (class "Default")
      (node (ref "J20") (pin "6") (pinfunction "MDI_2-_6") (pintype "passive"))
    )
    (net (code "80") (name "/RGMII_TR2_P") (class "Default")
      (node (ref "J20") (pin "5") (pinfunction "MDI_2+_5") (pintype "passive"))
    )
    (net (code "81") (name "/RGMII_TR3_N") (class "Default")
      (node (ref "J20") (pin "9") (pinfunction "MDI_3-_9") (pintype "passive"))
    )
    (net (code "82") (name "/RGMII_TR3_P") (class "Default")
      (node (ref "J20") (pin "8") (pinfunction "MDI_3+_8") (pintype "passive"))
    )
    (net (code "83") (name "/XADC_IN_N") (class "Default")
      (node (ref "R133") (pin "1") (pinfunction "1_1") (pintype "passive"))
    )
    (net (code "84") (name "/XADC_IN_P") (class "Default")
      (node (ref "R131") (pin "1") (pinfunction "1_1") (pintype "passive"))
    )
    (net (code "85") (name "/XADC_TEMP_N") (class "Default")
      (node (ref "R134") (pin "2") (pinfunction "2_2") (pintype "passive"))
    )
    (net (code "86") (name "/XADC_TEMP_P") (class "Default")
      (node (ref "R132") (pin "2") (pinfunction "2_2") (pintype "passive"))
    )
    (net (code "87") (name "GND") (class "Default")
      (node (ref "C119") (pin "1") (pinfunction "1_1") (pintype "passive"))
      (node (ref "C120") (pin "1") (pinfunction "1_1") (pintype "passive"))
      (node (ref "C121") (pin "1") (pinfunction "1_1") (pintype "passive"))
      (node (ref "D46") (pin "1") (pinfunction "1_1") (pintype "passive"))
      (node (ref "D47") (pin "1") (pinfunction "1_1") (pintype "passive"))
      (node (ref "D48") (pin "1") (pinfunction "1_1") (pintype "passive"))
      (node (ref "D49") (pin "1") (pinfunction "1_1") (pintype "passive"))
      (node (ref "D50") (pin "1") (pinfunction "1_1") (pintype "passive"))
      (node (ref "D51") (pin "1") (pinfunction "1_1") (pintype "passive"))
      (node (ref "D52") (pin "1") (pinfunction "1_1") (pintype "passive"))
      (node (ref "D53") (pin "1") (pinfunction "1_1") (pintype "passive"))
      (node (ref "D54") (pin "1") (pinfunction "1_1") (pintype "passive"))
      (node (ref "D55") (pin "1") (pinfunction "1_1") (pintype "passive"))
      (node (ref "D56") (pin "1") (pinfunction "1_1") (pintype "passive"))
      (node (ref "D57") (pin "1") (pinfunction "1_1") (pintype "passive"))
      (node (ref "D58") (pin "1") (pinfunction "1_1") (pintype "passive"))
      (node (ref "D59") (pin "1") (pinfunction "1_1") (pintype "passive"))
      (node (ref "D60") (pin "1") (pinfunction "1_1") (pintype "passive"))
      (node (ref "D61") (pin "1") (pinfunction "1_1") (pintype "passive"))
      (node (ref "D62") (pin "1") (pinfunction "1_1") (pintype "passive"))
      (node (ref "D63") (pin "1") (pinfunction "1_1") (pintype "passive"))
      (node (ref "D64") (pin "1") (pinfunction "1_1") (pintype "passive"))
      (node (ref "D65") (pin "1") (pinfunction "1_1") (pintype "passive"))
      (node (ref "D66") (pin "1") (pinfunction "1_1") (pintype "passive"))
      (node (ref "D67") (pin "1") (pinfunction "1_1") (pintype "passive"))
      (node (ref "D68") (pin "1") (pinfunction "1_1") (pintype "passive"))
      (node (ref "D69") (pin "1") (pinfunction "1_1") (pintype "passive"))
      (node (ref "D70") (pin "1") (pinfunction "1_1") (pintype "passive"))
      (node (ref "D71") (pin "1") (pinfunction "1_1") (pintype "passive"))
      (node (ref "D72") (pin "1") (pinfunction "1_1") (pintype "passive"))
      (node (ref "D73") (pin "1") (pinfunction "1_1") (pintype "passive"))
      (node (ref "D74") (pin "2") (pinfunction "A_2") (pintype "passive"))
      (node (ref "D75") (pin "2") (pinfunction "A_2") (pintype "passive"))
      (node (ref "D76") (pin "1") (pinfunction "1_1") (pintype "passive"))
      (node (ref "D77") (pin "1") (pinfunction "1_1") (pintype "passive"))
      (node (ref "D78") (pin "1") (pinfunction "1_1") (pintype "passive"))
      (node (ref "D79") (pin "1") (pinfunction "1_1") (pintype "passive"))
      (node (ref "D80") (pin "1") (pinfunction "1_1") (pintype "passive"))
      (node (ref "D81") (pin "1") (pinfunction "1_1") (pintype "passive"))
      (node (ref "D82") (pin "1") (pinfunction "1_1") (pintype "passive"))
      (node (ref "D83") (pin "1") (pinfunction "1_1") (pintype "passive"))
      (node (ref "J15") (pin "11") (pinfunction "11_11") (pintype "passive"))
      (node (ref "J15") (pin "5") (pinfunction "5_5") (pintype "passive"))
      (node (ref "J16") (pin "11") (pinfunction "11_11") (pintype "passive"))
      (node (ref "J16") (pin "5") (pinfunction "5_5") (pintype "passive"))
      (node (ref "J17") (pin "11") (pinfunction "11_11") (pintype "passive"))
      (node (ref "J17") (pin "5") (pinfunction "5_5") (pintype "passive"))
      (node (ref "J18") (pin "11") (pinfunction "11_11") (pintype "passive"))
      (node (ref "J18") (pin "5") (pinfunction "5_5") (pintype "passive"))
      (node (ref "J19") (pin "11") (pinfunction "11_11") (pintype "passive"))
      (node (ref "J19") (pin "5") (pinfunction "5_5") (pintype "passive"))
      (node (ref "J20") (pin "10") (pinfunction "CHS_10") (pintype "passive"))
      (node (ref "J20") (pin "15") (pinfunction "SHLD_15") (pintype "passive"))
      (node (ref "J20") (pin "16") (pinfunction "SHLD_16") (pintype "passive"))
      (node (ref "J21") (pin "4") (pinfunction "4_4") (pintype "passive"))
      (node (ref "U17") (pin "2") (pinfunction "GND_2") (pintype "passive"))
      (node (ref "U18") (pin "4") (pinfunction "GND_4") (pintype "passive"))
    )
    (net (code "88") (name "Net-(J20-CT)") (class "Default")
      (node (ref "C119") (pin "2") (pinfunction "2_2") (pintype "passive"))
      (node (ref "J20") (pin "1") (pinfunction "CT_1") (pintype "passive"))
    )
    (net (code "89") (name "Net-(J20-GRN_LED-)") (class "Default")
      (node (ref "J20") (pin "12") (pinfunction "GRN_LED-_12") (pintype "passive"))
      (node (ref "R135") (pin "1") (pinfunction "1_1") (pintype "passive"))
    )
    (net (code "90") (name "Net-(J20-YLW_LED-)") (class "Default")
      (node (ref "J20") (pin "13") (pinfunction "YLW_LED-_13") (pintype "passive"))
      (node (ref "R136") (pin "1") (pinfunction "1_1") (pintype "passive"))
    )
    (net (code "91") (name "Net-(U17-1Y)") (class "Default")
      (node (ref "R136") (pin "2") (pinfunction "2_2") (pintype "passive"))
      (node (ref "U17") (pin "6") (pinfunction "1Y_6") (pintype "passive"))
    )
    (net (code "92") (name "Net-(U17-2Y)") (class "Default")
      (node (ref "R135") (pin "2") (pinfunction "2_2") (pintype "passive"))
      (node (ref "U17") (pin "4") (pinfunction "2Y_4") (pintype "passive"))
    )
    (net (code "93") (name "Net-(U18-B1)") (class "Default")
      (node (ref "R155") (pin "1") (pinfunction "1_1") (pintype "passive"))
      (node (ref "U18") (pin "7") (pinfunction "B1_7") (pintype "passive"))
    )
    (net (code "94") (name "Net-(U18-B2)") (class "Default")
      (node (ref "R156") (pin "1") (pinfunction "1_1") (pintype "passive"))
      (node (ref "U18") (pin "6") (pinfunction "B2_6") (pintype "passive"))
    )
    (net (code "95") (name "Net-(U18-VCCB)") (class "Default")
      (node (ref "C121") (pin "2") (pinfunction "2_2") (pintype "passive"))
      (node (ref "R153") (pin "1") (pinfunction "1_1") (pintype "passive"))
      (node (ref "R154") (pin "1") (pinfunction "1_1") (pintype "passive"))
      (node (ref "U18") (pin "8") (pinfunction "VCCB_8") (pintype "passive"))
    )
    (net (code "96") (name "VDD_3V3") (class "Default")
      (node (ref "C120") (pin "2") (pinfunction "2_2") (pintype "passive"))
      (node (ref "J15") (pin "12") (pinfunction "12_12") (pintype "passive"))
      (node (ref "J15") (pin "6") (pinfunction "6_6") (pintype "passive"))
      (node (ref "J16") (pin "12") (pinfunction "12_12") (pintype "passive"))
      (node (ref "J16") (pin "6") (pinfunction "6_6") (pintype "passive"))
      (node (ref "J17") (pin "12") (pinfunction "12_12") (pintype "passive"))
      (node (ref "J17") (pin "6") (pinfunction "6_6") (pintype "passive"))
      (node (ref "J18") (pin "12") (pinfunction "12_12") (pintype "passive"))
      (node (ref "J18") (pin "6") (pinfunction "6_6") (pintype "passive"))
      (node (ref "J19") (pin "12") (pinfunction "12_12") (pintype "passive"))
      (node (ref "J19") (pin "6") (pinfunction "6_6") (pintype "passive"))
      (node (ref "J20") (pin "11") (pinfunction "GRN_LED+_11") (pintype "passive"))
      (node (ref "J20") (pin "14") (pinfunction "YLW_LED+_14") (pintype "passive"))
      (node (ref "J21") (pin "3") (pinfunction "3_3") (pintype "passive"))
      (node (ref "R154") (pin "2") (pinfunction "2_2") (pintype "passive"))
      (node (ref "U18") (pin "1") (pinfunction "VCCA_1") (pintype "passive"))
      (node (ref "U18") (pin "5") (pinfunction "OE_5") (pintype "passive"))
    )
    (net (code "97") (name "VDD_501_1V8") (class "Default")
      (node (ref "R153") (pin "2") (pinfunction "2_2") (pintype "passive"))
      (node (ref "U17") (pin "5") (pinfunction "VCC_5") (pintype "passive"))
    )
    (net (code "98") (name "unconnected-(J15-Pad3)") (class "Default")
      (node (ref "J15") (pin "3") (pinfunction "3_3") (pintype "passive+no_connect"))
    )
    (net (code "99") (name "unconnected-(J15-Pad4)") (class "Default")
      (node (ref "J15") (pin "4") (pinfunction "4_4") (pintype "passive+no_connect"))
    )
    (net (code "100") (name "unconnected-(J15-Pad9)") (class "Default")
      (node (ref "J15") (pin "9") (pinfunction "9_9") (pintype "passive+no_connect"))
    )
    (net (code "101") (name "unconnected-(J15-Pad10)") (class "Default")
      (node (ref "J15") (pin "10") (pinfunction "10_10") (pintype "passive+no_connect"))
    )
  )
)
